# sk6812-24-12ring-in.net
KiCad netlist of a schematic drawn in EAGLE
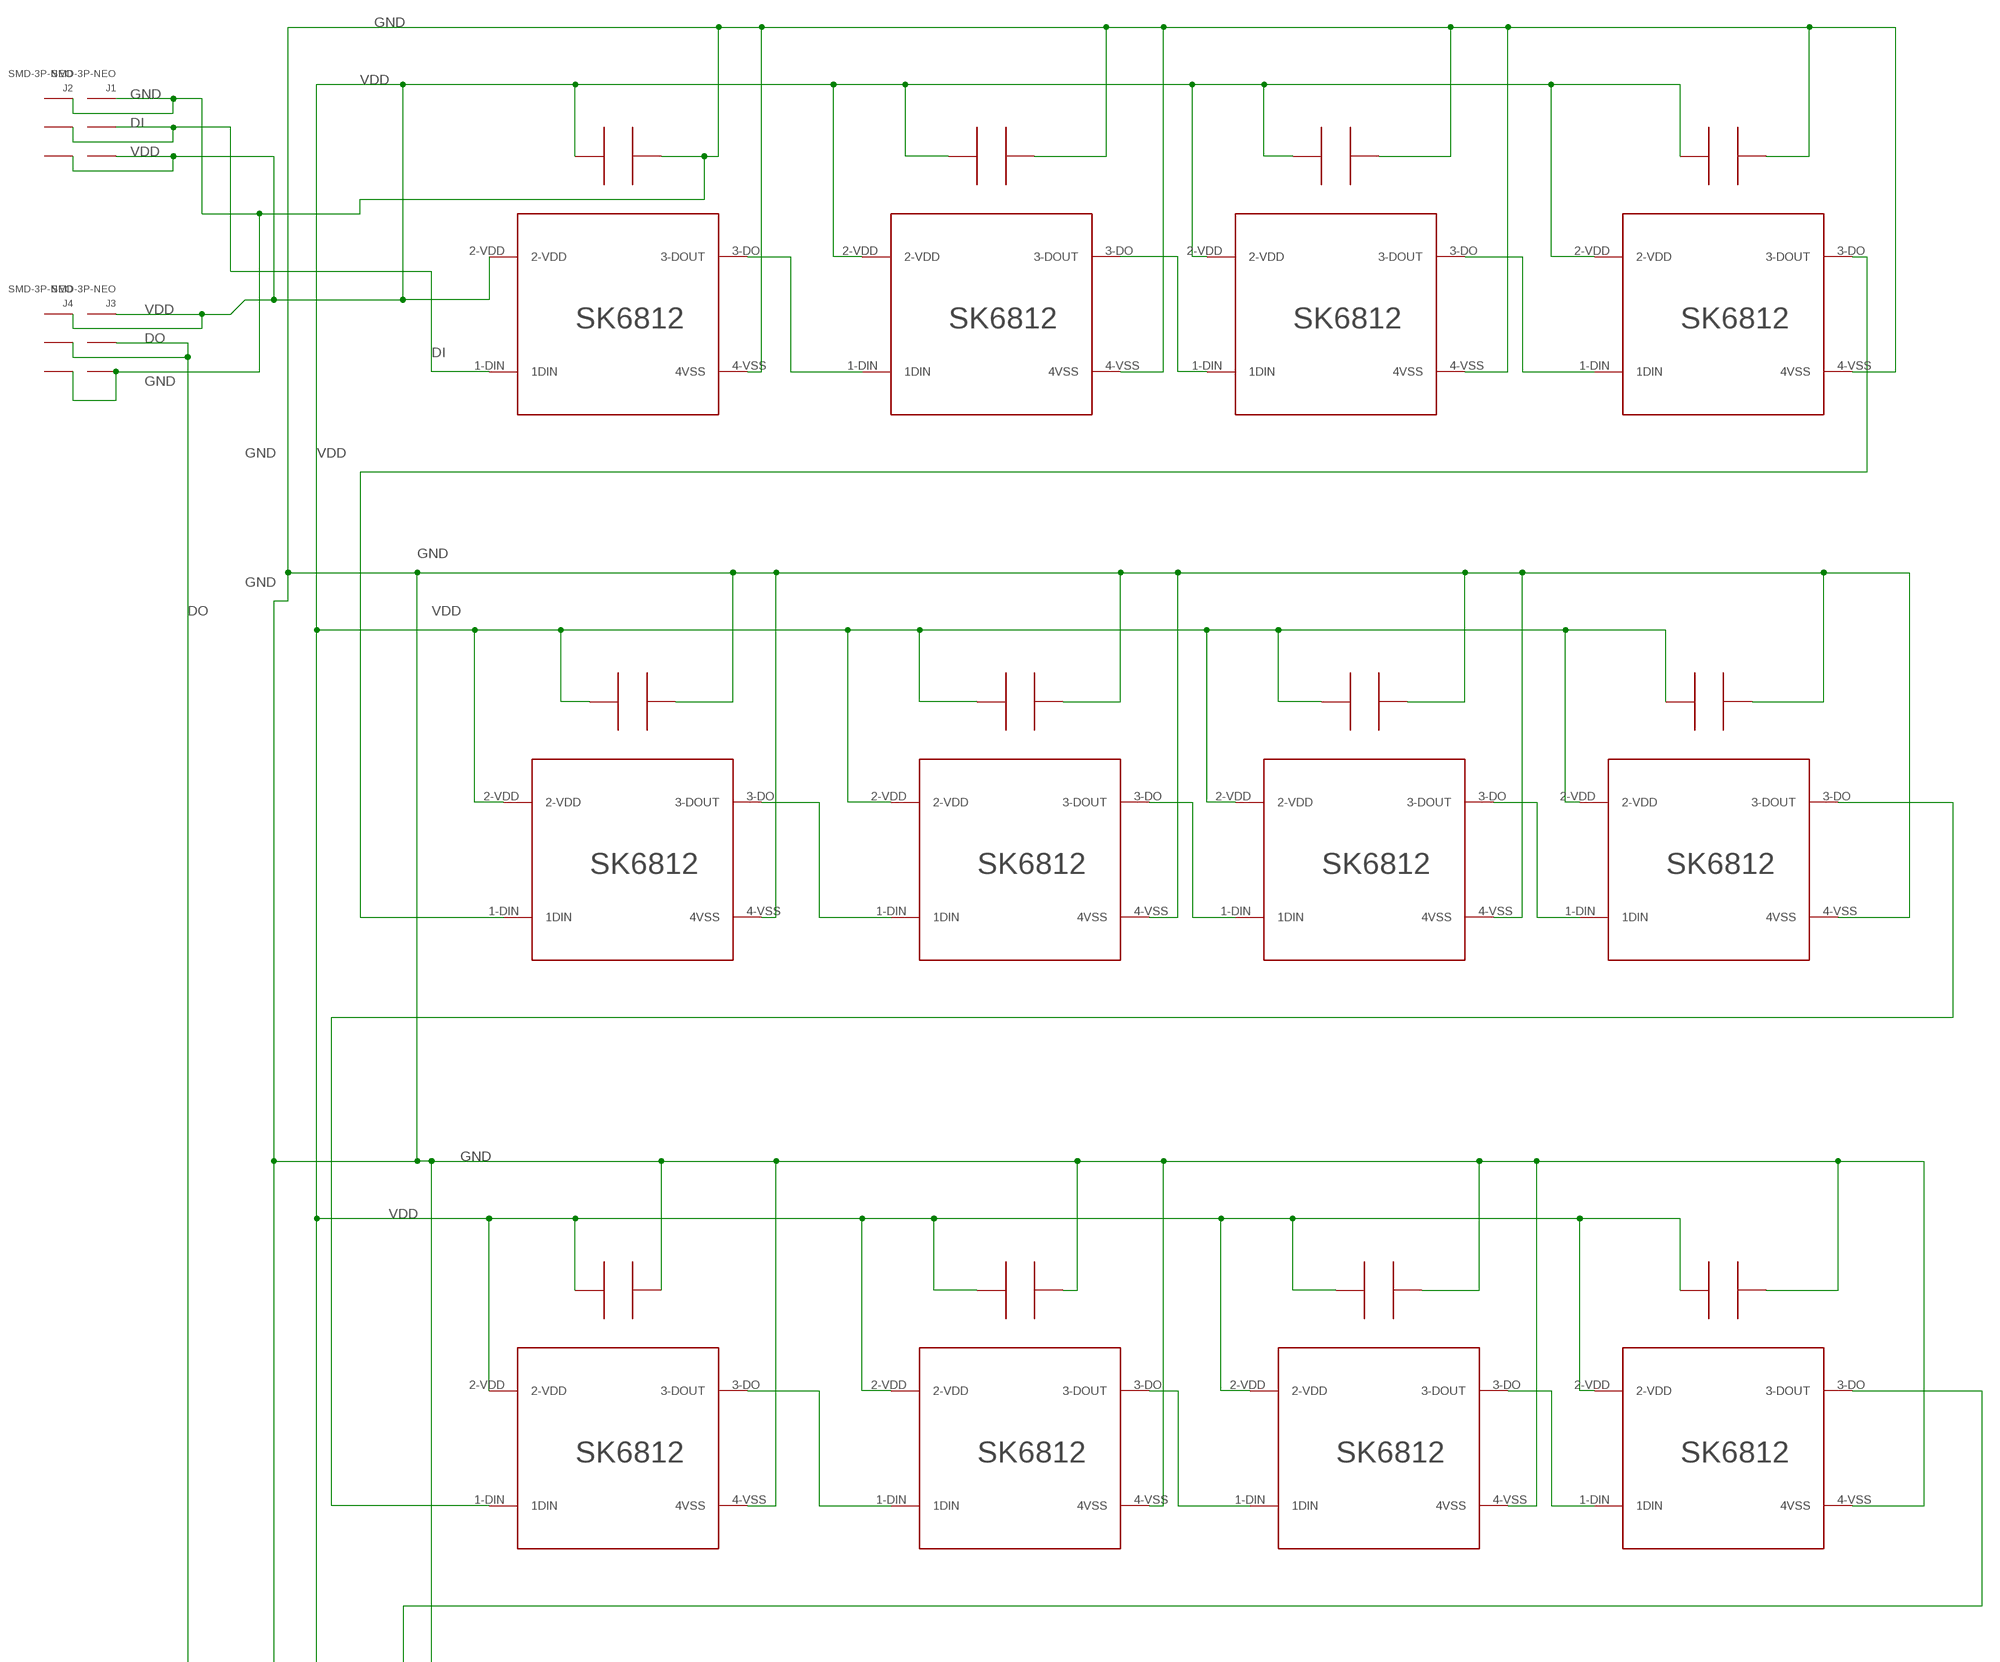
[diagram p0: schematic, sheet 1, part 1 of 2]
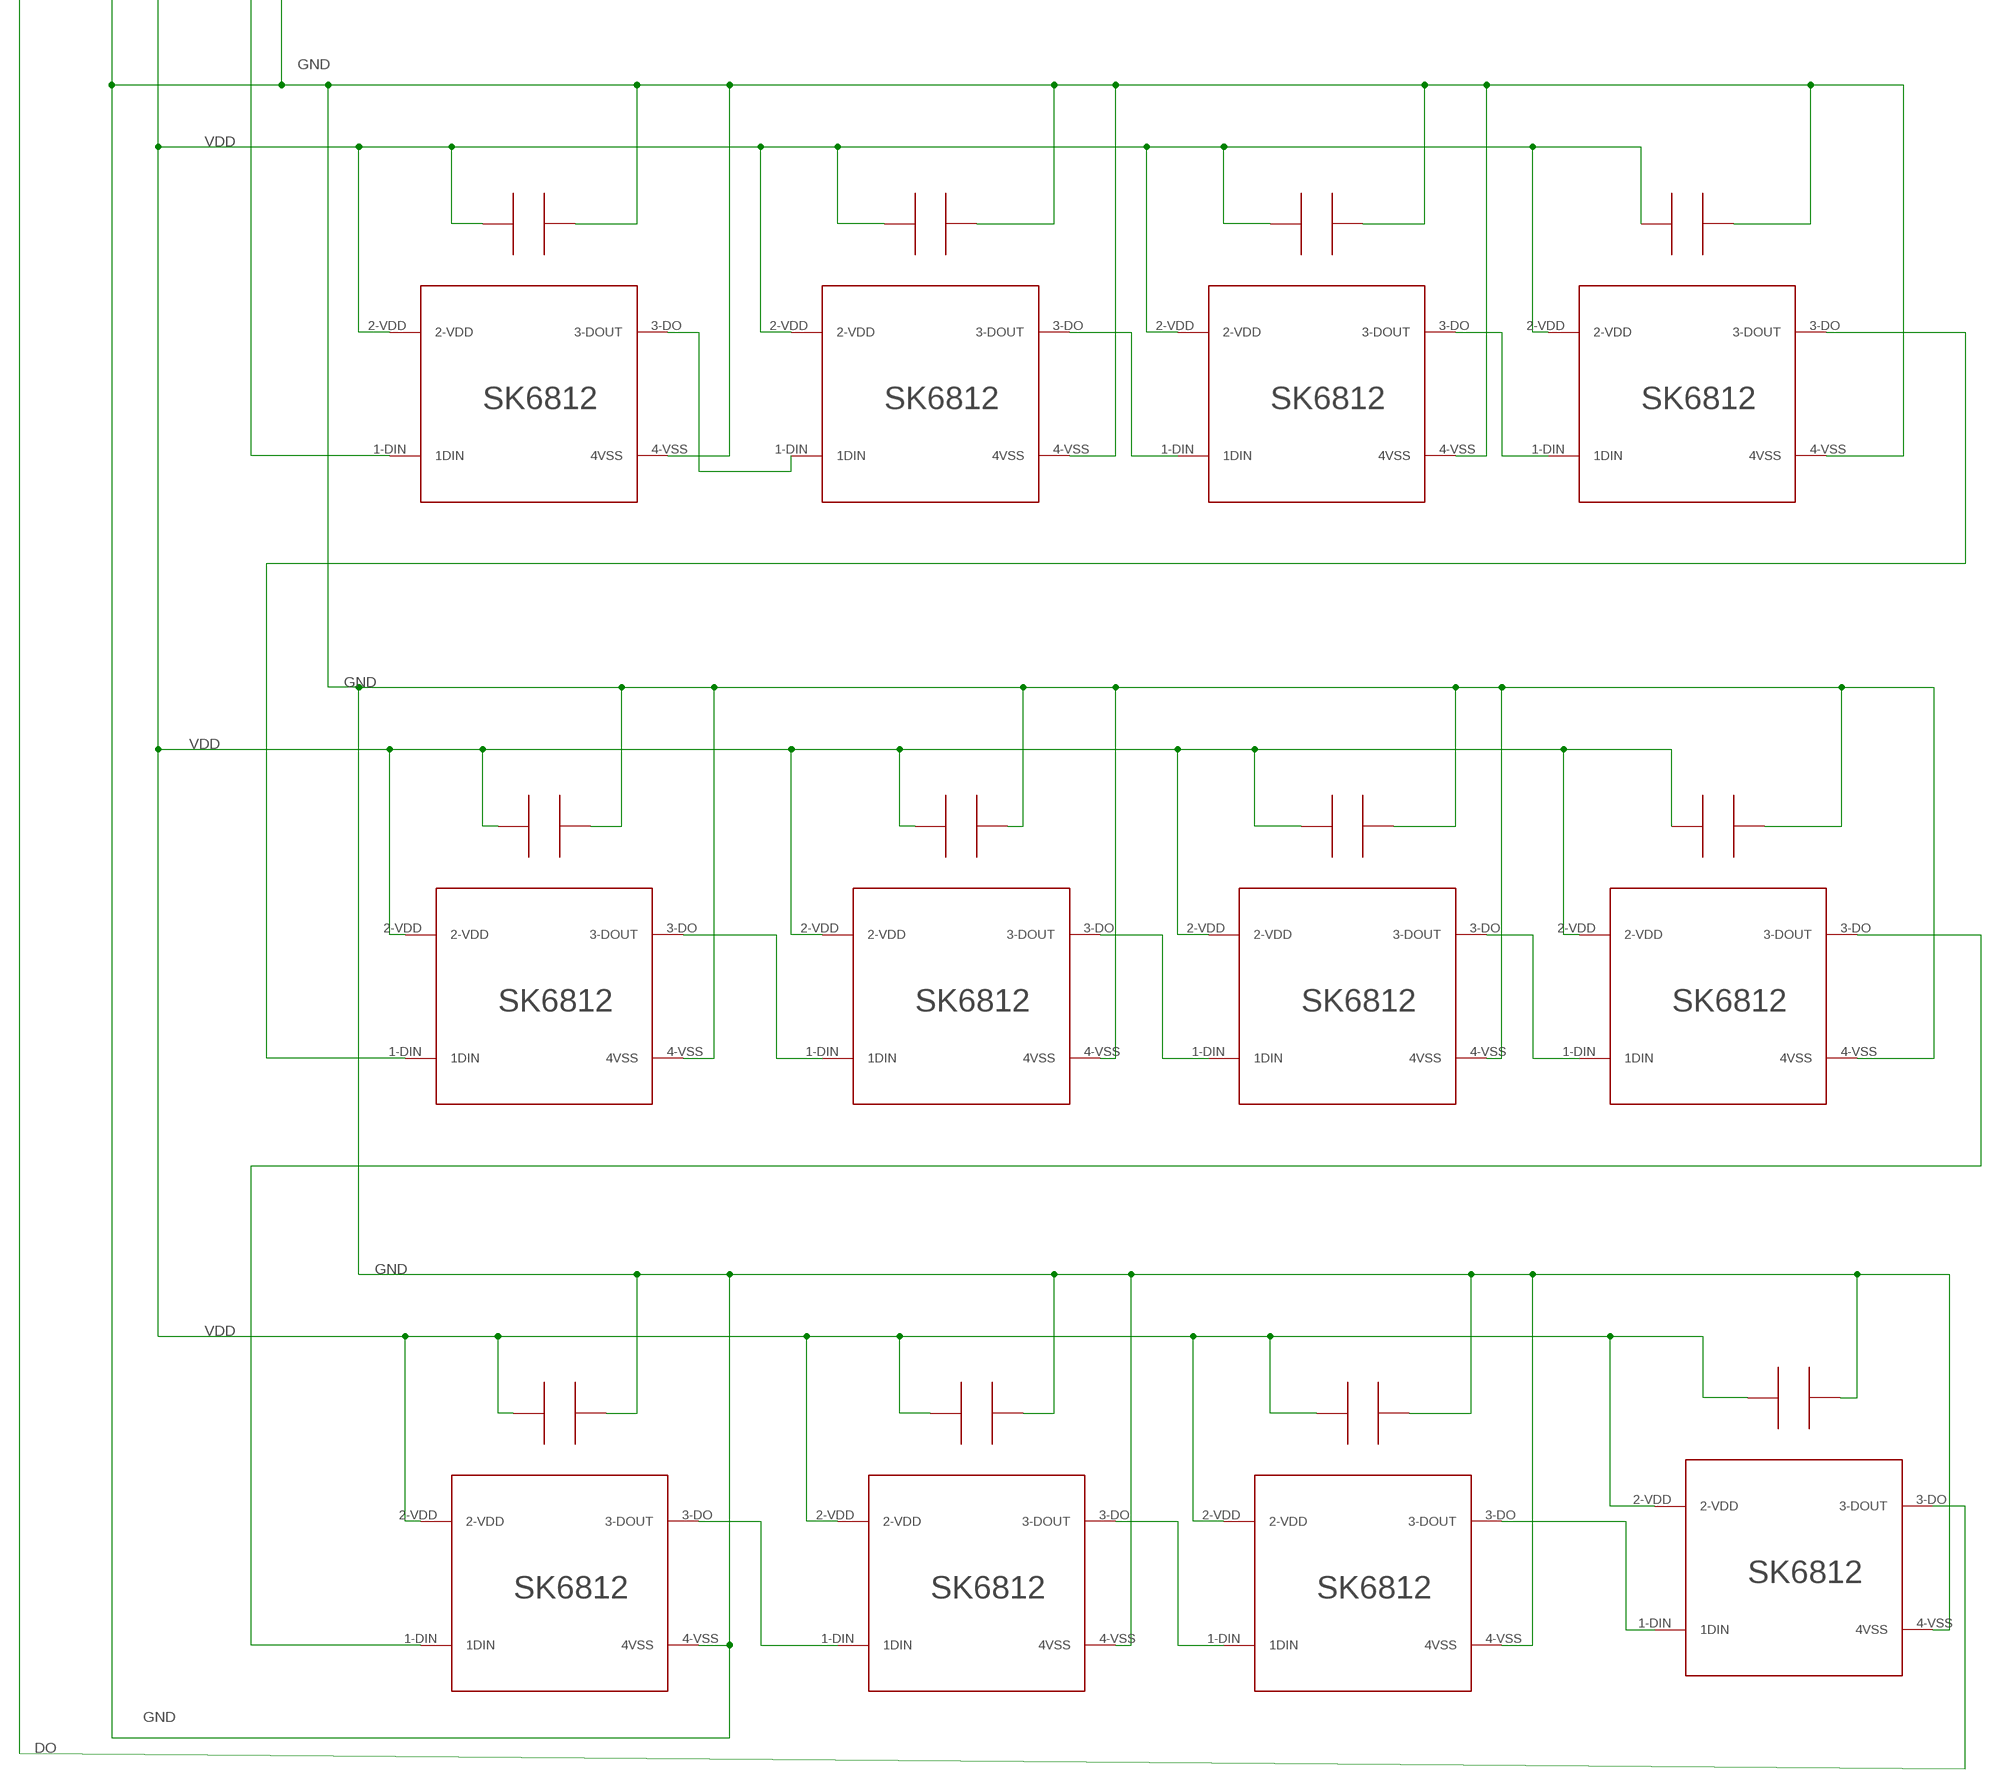
[diagram p1: schematic, sheet 1, part 2 of 2]

(export (version "E")
  (design (tool "Eeschema 10.0.6"))
  (components
    (comp (ref "D1")
      (value "SK6812-S-C")
      (footprint "eagle-import:SMD4020+0402C")
      (libsource (lib "eagle-import") (part "SK6812-S-C"))
    )
    (comp (ref "D2")
      (value "SK6812-S-C")
      (footprint "eagle-import:SMD4020+0402C")
      (libsource (lib "eagle-import") (part "SK6812-S-C"))
    )
    (comp (ref "D3")
      (value "SK6812-S-C")
      (footprint "eagle-import:SMD4020+0402C")
      (libsource (lib "eagle-import") (part "SK6812-S-C"))
    )
    (comp (ref "D4")
      (value "SK6812-S-C")
      (footprint "eagle-import:SMD4020+0402C")
      (libsource (lib "eagle-import") (part "SK6812-S-C"))
    )
    (comp (ref "D5")
      (value "SK6812-S-C")
      (footprint "eagle-import:SMD4020+0402C")
      (libsource (lib "eagle-import") (part "SK6812-S-C"))
    )
    (comp (ref "D6")
      (value "SK6812-S-C")
      (footprint "eagle-import:SMD4020+0402C")
      (libsource (lib "eagle-import") (part "SK6812-S-C"))
    )
    (comp (ref "D7")
      (value "SK6812-S-C")
      (footprint "eagle-import:SMD4020+0402C")
      (libsource (lib "eagle-import") (part "SK6812-S-C"))
    )
    (comp (ref "D8")
      (value "SK6812-S-C")
      (footprint "eagle-import:SMD4020+0402C")
      (libsource (lib "eagle-import") (part "SK6812-S-C"))
    )
    (comp (ref "D9")
      (value "SK6812-S-C")
      (footprint "eagle-import:SMD4020+0402C")
      (libsource (lib "eagle-import") (part "SK6812-S-C"))
    )
    (comp (ref "D10")
      (value "SK6812-S-C")
      (footprint "eagle-import:SMD4020+0402C")
      (libsource (lib "eagle-import") (part "SK6812-S-C"))
    )
    (comp (ref "D11")
      (value "SK6812-S-C")
      (footprint "eagle-import:SMD4020+0402C")
      (libsource (lib "eagle-import") (part "SK6812-S-C"))
    )
    (comp (ref "D12")
      (value "SK6812-S-C")
      (footprint "eagle-import:SMD4020+0402C")
      (libsource (lib "eagle-import") (part "SK6812-S-C"))
    )
    (comp (ref "D13")
      (value "SK6812-S-C")
      (footprint "eagle-import:SMD4020+0402C")
      (libsource (lib "eagle-import") (part "SK6812-S-C"))
    )
    (comp (ref "D14")
      (value "SK6812-S-C")
      (footprint "eagle-import:SMD4020+0402C")
      (libsource (lib "eagle-import") (part "SK6812-S-C"))
    )
    (comp (ref "D15")
      (value "SK6812-S-C")
      (footprint "eagle-import:SMD4020+0402C")
      (libsource (lib "eagle-import") (part "SK6812-S-C"))
    )
    (comp (ref "D16")
      (value "SK6812-S-C")
      (footprint "eagle-import:SMD4020+0402C")
      (libsource (lib "eagle-import") (part "SK6812-S-C"))
    )
    (comp (ref "D17")
      (value "SK6812-S-C")
      (footprint "eagle-import:SMD4020+0402C")
      (libsource (lib "eagle-import") (part "SK6812-S-C"))
    )
    (comp (ref "D18")
      (value "SK6812-S-C")
      (footprint "eagle-import:SMD4020+0402C")
      (libsource (lib "eagle-import") (part "SK6812-S-C"))
    )
    (comp (ref "D19")
      (value "SK6812-S-C")
      (footprint "eagle-import:SMD4020+0402C")
      (libsource (lib "eagle-import") (part "SK6812-S-C"))
    )
    (comp (ref "D20")
      (value "SK6812-S-C")
      (footprint "eagle-import:SMD4020+0402C")
      (libsource (lib "eagle-import") (part "SK6812-S-C"))
    )
    (comp (ref "D21")
      (value "SK6812-S-C")
      (footprint "eagle-import:SMD4020+0402C")
      (libsource (lib "eagle-import") (part "SK6812-S-C"))
    )
    (comp (ref "D22")
      (value "SK6812-S-C")
      (footprint "eagle-import:SMD4020+0402C")
      (libsource (lib "eagle-import") (part "SK6812-S-C"))
    )
    (comp (ref "D23")
      (value "SK6812-S-C")
      (footprint "eagle-import:SMD4020+0402C")
      (libsource (lib "eagle-import") (part "SK6812-S-C"))
    )
    (comp (ref "D24")
      (value "SK6812-S-C")
      (footprint "eagle-import:SMD4020+0402C")
      (libsource (lib "eagle-import") (part "SK6812-S-C"))
    )
    (comp (ref "J1")
      (value "SMD-3P-NEO")
      (footprint "eagle-import:SMD-3P-2.0")
      (libsource (lib "eagle-import") (part "SMD-3P-NEO"))
    )
    (comp (ref "J2")
      (value "SMD-3P-NEO")
      (footprint "eagle-import:SMD-3P-2.0")
      (libsource (lib "eagle-import") (part "SMD-3P-NEO"))
    )
    (comp (ref "J3")
      (value "SMD-3P-NEO")
      (footprint "eagle-import:SMD-3P-2.0")
      (libsource (lib "eagle-import") (part "SMD-3P-NEO"))
    )
    (comp (ref "J4")
      (value "SMD-3P-NEO")
      (footprint "eagle-import:SMD-3P-2.0")
      (libsource (lib "eagle-import") (part "SMD-3P-NEO"))
    )
  )
  (nets
    (net (code "1") (name "/DI") (class "Default")
      (node (ref "D1") (pin "1-DIN") (pinfunction "1DIN_1-DIN") (pintype "bidirectional"))
      (node (ref "J1") (pin "P$2") (pinfunction "2_P$2") (pintype "bidirectional"))
      (node (ref "J2") (pin "P$2") (pinfunction "2_P$2") (pintype "bidirectional"))
    )
    (net (code "2") (name "/DO") (class "Default")
      (node (ref "D24") (pin "3-DO") (pinfunction "3-DOUT_3-DO") (pintype "bidirectional"))
      (node (ref "J3") (pin "P$2") (pinfunction "2_P$2") (pintype "bidirectional"))
      (node (ref "J4") (pin "P$2") (pinfunction "2_P$2") (pintype "bidirectional"))
    )
    (net (code "3") (name "/GND") (class "Default")
      (node (ref "D1") (pin "4-VSS") (pinfunction "4VSS_4-VSS") (pintype "bidirectional"))
      (node (ref "D1") (pin "5-C-VSS") (pinfunction "C-VSS_5-C-VSS") (pintype "bidirectional"))
      (node (ref "D10") (pin "4-VSS") (pinfunction "4VSS_4-VSS") (pintype "bidirectional"))
      (node (ref "D10") (pin "5-C-VSS") (pinfunction "C-VSS_5-C-VSS") (pintype "bidirectional"))
      (node (ref "D11") (pin "4-VSS") (pinfunction "4VSS_4-VSS") (pintype "bidirectional"))
      (node (ref "D11") (pin "5-C-VSS") (pinfunction "C-VSS_5-C-VSS") (pintype "bidirectional"))
      (node (ref "D12") (pin "4-VSS") (pinfunction "4VSS_4-VSS") (pintype "bidirectional"))
      (node (ref "D12") (pin "5-C-VSS") (pinfunction "C-VSS_5-C-VSS") (pintype "bidirectional"))
      (node (ref "D13") (pin "4-VSS") (pinfunction "4VSS_4-VSS") (pintype "bidirectional"))
      (node (ref "D13") (pin "5-C-VSS") (pinfunction "C-VSS_5-C-VSS") (pintype "bidirectional"))
      (node (ref "D14") (pin "4-VSS") (pinfunction "4VSS_4-VSS") (pintype "bidirectional"))
      (node (ref "D14") (pin "5-C-VSS") (pinfunction "C-VSS_5-C-VSS") (pintype "bidirectional"))
      (node (ref "D15") (pin "4-VSS") (pinfunction "4VSS_4-VSS") (pintype "bidirectional"))
      (node (ref "D15") (pin "5-C-VSS") (pinfunction "C-VSS_5-C-VSS") (pintype "bidirectional"))
      (node (ref "D16") (pin "4-VSS") (pinfunction "4VSS_4-VSS") (pintype "bidirectional"))
      (node (ref "D16") (pin "5-C-VSS") (pinfunction "C-VSS_5-C-VSS") (pintype "bidirectional"))
      (node (ref "D17") (pin "4-VSS") (pinfunction "4VSS_4-VSS") (pintype "bidirectional"))
      (node (ref "D17") (pin "5-C-VSS") (pinfunction "C-VSS_5-C-VSS") (pintype "bidirectional"))
      (node (ref "D18") (pin "4-VSS") (pinfunction "4VSS_4-VSS") (pintype "bidirectional"))
      (node (ref "D18") (pin "5-C-VSS") (pinfunction "C-VSS_5-C-VSS") (pintype "bidirectional"))
      (node (ref "D19") (pin "4-VSS") (pinfunction "4VSS_4-VSS") (pintype "bidirectional"))
      (node (ref "D19") (pin "5-C-VSS") (pinfunction "C-VSS_5-C-VSS") (pintype "bidirectional"))
      (node (ref "D2") (pin "4-VSS") (pinfunction "4VSS_4-VSS") (pintype "bidirectional"))
      (node (ref "D2") (pin "5-C-VSS") (pinfunction "C-VSS_5-C-VSS") (pintype "bidirectional"))
      (node (ref "D20") (pin "4-VSS") (pinfunction "4VSS_4-VSS") (pintype "bidirectional"))
      (node (ref "D20") (pin "5-C-VSS") (pinfunction "C-VSS_5-C-VSS") (pintype "bidirectional"))
      (node (ref "D21") (pin "4-VSS") (pinfunction "4VSS_4-VSS") (pintype "bidirectional"))
      (node (ref "D21") (pin "5-C-VSS") (pinfunction "C-VSS_5-C-VSS") (pintype "bidirectional"))
      (node (ref "D22") (pin "4-VSS") (pinfunction "4VSS_4-VSS") (pintype "bidirectional"))
      (node (ref "D22") (pin "5-C-VSS") (pinfunction "C-VSS_5-C-VSS") (pintype "bidirectional"))
      (node (ref "D23") (pin "4-VSS") (pinfunction "4VSS_4-VSS") (pintype "bidirectional"))
      (node (ref "D23") (pin "5-C-VSS") (pinfunction "C-VSS_5-C-VSS") (pintype "bidirectional"))
      (node (ref "D24") (pin "4-VSS") (pinfunction "4VSS_4-VSS") (pintype "bidirectional"))
      (node (ref "D24") (pin "5-C-VSS") (pinfunction "C-VSS_5-C-VSS") (pintype "bidirectional"))
      (node (ref "D3") (pin "4-VSS") (pinfunction "4VSS_4-VSS") (pintype "bidirectional"))
      (node (ref "D3") (pin "5-C-VSS") (pinfunction "C-VSS_5-C-VSS") (pintype "bidirectional"))
      (node (ref "D4") (pin "4-VSS") (pinfunction "4VSS_4-VSS") (pintype "bidirectional"))
      (node (ref "D4") (pin "5-C-VSS") (pinfunction "C-VSS_5-C-VSS") (pintype "bidirectional"))
      (node (ref "D5") (pin "4-VSS") (pinfunction "4VSS_4-VSS") (pintype "bidirectional"))
      (node (ref "D5") (pin "5-C-VSS") (pinfunction "C-VSS_5-C-VSS") (pintype "bidirectional"))
      (node (ref "D6") (pin "4-VSS") (pinfunction "4VSS_4-VSS") (pintype "bidirectional"))
      (node (ref "D6") (pin "5-C-VSS") (pinfunction "C-VSS_5-C-VSS") (pintype "bidirectional"))
      (node (ref "D7") (pin "4-VSS") (pinfunction "4VSS_4-VSS") (pintype "bidirectional"))
      (node (ref "D7") (pin "5-C-VSS") (pinfunction "C-VSS_5-C-VSS") (pintype "bidirectional"))
      (node (ref "D8") (pin "4-VSS") (pinfunction "4VSS_4-VSS") (pintype "bidirectional"))
      (node (ref "D8") (pin "5-C-VSS") (pinfunction "C-VSS_5-C-VSS") (pintype "bidirectional"))
      (node (ref "D9") (pin "4-VSS") (pinfunction "4VSS_4-VSS") (pintype "bidirectional"))
      (node (ref "D9") (pin "5-C-VSS") (pinfunction "C-VSS_5-C-VSS") (pintype "bidirectional"))
      (node (ref "J1") (pin "P$3") (pinfunction "3_P$3") (pintype "bidirectional"))
      (node (ref "J2") (pin "P$3") (pinfunction "3_P$3") (pintype "bidirectional"))
      (node (ref "J3") (pin "P$1") (pinfunction "1_P$1") (pintype "bidirectional"))
      (node (ref "J4") (pin "P$1") (pinfunction "1_P$1") (pintype "bidirectional"))
    )
    (net (code "4") (name "/VDD") (class "Default")
      (node (ref "D1") (pin "2-VDD") (pinfunction "2-VDD_2-VDD") (pintype "bidirectional"))
      (node (ref "D1") (pin "6-C-VDD") (pinfunction "C-VDD_6-C-VDD") (pintype "bidirectional"))
      (node (ref "D10") (pin "2-VDD") (pinfunction "2-VDD_2-VDD") (pintype "bidirectional"))
      (node (ref "D10") (pin "6-C-VDD") (pinfunction "C-VDD_6-C-VDD") (pintype "bidirectional"))
      (node (ref "D11") (pin "2-VDD") (pinfunction "2-VDD_2-VDD") (pintype "bidirectional"))
      (node (ref "D11") (pin "6-C-VDD") (pinfunction "C-VDD_6-C-VDD") (pintype "bidirectional"))
      (node (ref "D12") (pin "2-VDD") (pinfunction "2-VDD_2-VDD") (pintype "bidirectional"))
      (node (ref "D12") (pin "6-C-VDD") (pinfunction "C-VDD_6-C-VDD") (pintype "bidirectional"))
      (node (ref "D13") (pin "2-VDD") (pinfunction "2-VDD_2-VDD") (pintype "bidirectional"))
      (node (ref "D13") (pin "6-C-VDD") (pinfunction "C-VDD_6-C-VDD") (pintype "bidirectional"))
      (node (ref "D14") (pin "2-VDD") (pinfunction "2-VDD_2-VDD") (pintype "bidirectional"))
      (node (ref "D14") (pin "6-C-VDD") (pinfunction "C-VDD_6-C-VDD") (pintype "bidirectional"))
      (node (ref "D15") (pin "2-VDD") (pinfunction "2-VDD_2-VDD") (pintype "bidirectional"))
      (node (ref "D15") (pin "6-C-VDD") (pinfunction "C-VDD_6-C-VDD") (pintype "bidirectional"))
      (node (ref "D16") (pin "2-VDD") (pinfunction "2-VDD_2-VDD") (pintype "bidirectional"))
      (node (ref "D16") (pin "6-C-VDD") (pinfunction "C-VDD_6-C-VDD") (pintype "bidirectional"))
      (node (ref "D17") (pin "2-VDD") (pinfunction "2-VDD_2-VDD") (pintype "bidirectional"))
      (node (ref "D17") (pin "6-C-VDD") (pinfunction "C-VDD_6-C-VDD") (pintype "bidirectional"))
      (node (ref "D18") (pin "2-VDD") (pinfunction "2-VDD_2-VDD") (pintype "bidirectional"))
      (node (ref "D18") (pin "6-C-VDD") (pinfunction "C-VDD_6-C-VDD") (pintype "bidirectional"))
      (node (ref "D19") (pin "2-VDD") (pinfunction "2-VDD_2-VDD") (pintype "bidirectional"))
      (node (ref "D19") (pin "6-C-VDD") (pinfunction "C-VDD_6-C-VDD") (pintype "bidirectional"))
      (node (ref "D2") (pin "2-VDD") (pinfunction "2-VDD_2-VDD") (pintype "bidirectional"))
      (node (ref "D2") (pin "6-C-VDD") (pinfunction "C-VDD_6-C-VDD") (pintype "bidirectional"))
      (node (ref "D20") (pin "2-VDD") (pinfunction "2-VDD_2-VDD") (pintype "bidirectional"))
      (node (ref "D20") (pin "6-C-VDD") (pinfunction "C-VDD_6-C-VDD") (pintype "bidirectional"))
      (node (ref "D21") (pin "2-VDD") (pinfunction "2-VDD_2-VDD") (pintype "bidirectional"))
      (node (ref "D21") (pin "6-C-VDD") (pinfunction "C-VDD_6-C-VDD") (pintype "bidirectional"))
      (node (ref "D22") (pin "2-VDD") (pinfunction "2-VDD_2-VDD") (pintype "bidirectional"))
      (node (ref "D22") (pin "6-C-VDD") (pinfunction "C-VDD_6-C-VDD") (pintype "bidirectional"))
      (node (ref "D23") (pin "2-VDD") (pinfunction "2-VDD_2-VDD") (pintype "bidirectional"))
      (node (ref "D23") (pin "6-C-VDD") (pinfunction "C-VDD_6-C-VDD") (pintype "bidirectional"))
      (node (ref "D24") (pin "2-VDD") (pinfunction "2-VDD_2-VDD") (pintype "bidirectional"))
      (node (ref "D24") (pin "6-C-VDD") (pinfunction "C-VDD_6-C-VDD") (pintype "bidirectional"))
      (node (ref "D3") (pin "2-VDD") (pinfunction "2-VDD_2-VDD") (pintype "bidirectional"))
      (node (ref "D3") (pin "6-C-VDD") (pinfunction "C-VDD_6-C-VDD") (pintype "bidirectional"))
      (node (ref "D4") (pin "2-VDD") (pinfunction "2-VDD_2-VDD") (pintype "bidirectional"))
      (node (ref "D4") (pin "6-C-VDD") (pinfunction "C-VDD_6-C-VDD") (pintype "bidirectional"))
      (node (ref "D5") (pin "2-VDD") (pinfunction "2-VDD_2-VDD") (pintype "bidirectional"))
      (node (ref "D5") (pin "6-C-VDD") (pinfunction "C-VDD_6-C-VDD") (pintype "bidirectional"))
      (node (ref "D6") (pin "2-VDD") (pinfunction "2-VDD_2-VDD") (pintype "bidirectional"))
      (node (ref "D6") (pin "6-C-VDD") (pinfunction "C-VDD_6-C-VDD") (pintype "bidirectional"))
      (node (ref "D7") (pin "2-VDD") (pinfunction "2-VDD_2-VDD") (pintype "bidirectional"))
      (node (ref "D7") (pin "6-C-VDD") (pinfunction "C-VDD_6-C-VDD") (pintype "bidirectional"))
      (node (ref "D8") (pin "2-VDD") (pinfunction "2-VDD_2-VDD") (pintype "bidirectional"))
      (node (ref "D8") (pin "6-C-VDD") (pinfunction "C-VDD_6-C-VDD") (pintype "bidirectional"))
      (node (ref "D9") (pin "2-VDD") (pinfunction "2-VDD_2-VDD") (pintype "bidirectional"))
      (node (ref "D9") (pin "6-C-VDD") (pinfunction "C-VDD_6-C-VDD") (pintype "bidirectional"))
      (node (ref "J1") (pin "P$1") (pinfunction "1_P$1") (pintype "bidirectional"))
      (node (ref "J2") (pin "P$1") (pinfunction "1_P$1") (pintype "bidirectional"))
      (node (ref "J3") (pin "P$3") (pinfunction "3_P$3") (pintype "bidirectional"))
      (node (ref "J4") (pin "P$3") (pinfunction "3_P$3") (pintype "bidirectional"))
    )
    (net (code "5") (name "Net-(D1-3-DOUT)") (class "Default")
      (node (ref "D1") (pin "3-DO") (pinfunction "3-DOUT_3-DO") (pintype "bidirectional"))
      (node (ref "D2") (pin "1-DIN") (pinfunction "1DIN_1-DIN") (pintype "bidirectional"))
    )
    (net (code "6") (name "Net-(D2-3-DOUT)") (class "Default")
      (node (ref "D2") (pin "3-DO") (pinfunction "3-DOUT_3-DO") (pintype "bidirectional"))
      (node (ref "D3") (pin "1-DIN") (pinfunction "1DIN_1-DIN") (pintype "bidirectional"))
    )
    (net (code "7") (name "Net-(D3-3-DOUT)") (class "Default")
      (node (ref "D3") (pin "3-DO") (pinfunction "3-DOUT_3-DO") (pintype "bidirectional"))
      (node (ref "D4") (pin "1-DIN") (pinfunction "1DIN_1-DIN") (pintype "bidirectional"))
    )
    (net (code "8") (name "Net-(D4-3-DOUT)") (class "Default")
      (node (ref "D4") (pin "3-DO") (pinfunction "3-DOUT_3-DO") (pintype "bidirectional"))
      (node (ref "D5") (pin "1-DIN") (pinfunction "1DIN_1-DIN") (pintype "bidirectional"))
    )
    (net (code "9") (name "Net-(D5-3-DOUT)") (class "Default")
      (node (ref "D5") (pin "3-DO") (pinfunction "3-DOUT_3-DO") (pintype "bidirectional"))
      (node (ref "D6") (pin "1-DIN") (pinfunction "1DIN_1-DIN") (pintype "bidirectional"))
    )
    (net (code "10") (name "Net-(D6-3-DOUT)") (class "Default")
      (node (ref "D6") (pin "3-DO") (pinfunction "3-DOUT_3-DO") (pintype "bidirectional"))
      (node (ref "D7") (pin "1-DIN") (pinfunction "1DIN_1-DIN") (pintype "bidirectional"))
    )
    (net (code "11") (name "Net-(D7-3-DOUT)") (class "Default")
      (node (ref "D7") (pin "3-DO") (pinfunction "3-DOUT_3-DO") (pintype "bidirectional"))
      (node (ref "D8") (pin "1-DIN") (pinfunction "1DIN_1-DIN") (pintype "bidirectional"))
    )
    (net (code "12") (name "Net-(D8-3-DOUT)") (class "Default")
      (node (ref "D8") (pin "3-DO") (pinfunction "3-DOUT_3-DO") (pintype "bidirectional"))
      (node (ref "D9") (pin "1-DIN") (pinfunction "1DIN_1-DIN") (pintype "bidirectional"))
    )
    (net (code "13") (name "Net-(D10-1DIN)") (class "Default")
      (node (ref "D10") (pin "1-DIN") (pinfunction "1DIN_1-DIN") (pintype "bidirectional"))
      (node (ref "D9") (pin "3-DO") (pinfunction "3-DOUT_3-DO") (pintype "bidirectional"))
    )
    (net (code "14") (name "Net-(D10-3-DOUT)") (class "Default")
      (node (ref "D10") (pin "3-DO") (pinfunction "3-DOUT_3-DO") (pintype "bidirectional"))
      (node (ref "D11") (pin "1-DIN") (pinfunction "1DIN_1-DIN") (pintype "bidirectional"))
    )
    (net (code "15") (name "Net-(D11-3-DOUT)") (class "Default")
      (node (ref "D11") (pin "3-DO") (pinfunction "3-DOUT_3-DO") (pintype "bidirectional"))
      (node (ref "D12") (pin "1-DIN") (pinfunction "1DIN_1-DIN") (pintype "bidirectional"))
    )
    (net (code "16") (name "Net-(D12-3-DOUT)") (class "Default")
      (node (ref "D12") (pin "3-DO") (pinfunction "3-DOUT_3-DO") (pintype "bidirectional"))
      (node (ref "D13") (pin "1-DIN") (pinfunction "1DIN_1-DIN") (pintype "bidirectional"))
    )
    (net (code "17") (name "Net-(D13-3-DOUT)") (class "Default")
      (node (ref "D13") (pin "3-DO") (pinfunction "3-DOUT_3-DO") (pintype "bidirectional"))
      (node (ref "D14") (pin "1-DIN") (pinfunction "1DIN_1-DIN") (pintype "bidirectional"))
    )
    (net (code "18") (name "Net-(D14-3-DOUT)") (class "Default")
      (node (ref "D14") (pin "3-DO") (pinfunction "3-DOUT_3-DO") (pintype "bidirectional"))
      (node (ref "D15") (pin "1-DIN") (pinfunction "1DIN_1-DIN") (pintype "bidirectional"))
    )
    (net (code "19") (name "Net-(D15-3-DOUT)") (class "Default")
      (node (ref "D15") (pin "3-DO") (pinfunction "3-DOUT_3-DO") (pintype "bidirectional"))
      (node (ref "D16") (pin "1-DIN") (pinfunction "1DIN_1-DIN") (pintype "bidirectional"))
    )
    (net (code "20") (name "Net-(D16-3-DOUT)") (class "Default")
      (node (ref "D16") (pin "3-DO") (pinfunction "3-DOUT_3-DO") (pintype "bidirectional"))
      (node (ref "D17") (pin "1-DIN") (pinfunction "1DIN_1-DIN") (pintype "bidirectional"))
    )
    (net (code "21") (name "Net-(D17-3-DOUT)") (class "Default")
      (node (ref "D17") (pin "3-DO") (pinfunction "3-DOUT_3-DO") (pintype "bidirectional"))
      (node (ref "D18") (pin "1-DIN") (pinfunction "1DIN_1-DIN") (pintype "bidirectional"))
    )
    (net (code "22") (name "Net-(D18-3-DOUT)") (class "Default")
      (node (ref "D18") (pin "3-DO") (pinfunction "3-DOUT_3-DO") (pintype "bidirectional"))
      (node (ref "D19") (pin "1-DIN") (pinfunction "1DIN_1-DIN") (pintype "bidirectional"))
    )
    (net (code "23") (name "Net-(D19-3-DOUT)") (class "Default")
      (node (ref "D19") (pin "3-DO") (pinfunction "3-DOUT_3-DO") (pintype "bidirectional"))
      (node (ref "D20") (pin "1-DIN") (pinfunction "1DIN_1-DIN") (pintype "bidirectional"))
    )
    (net (code "24") (name "Net-(D20-3-DOUT)") (class "Default")
      (node (ref "D20") (pin "3-DO") (pinfunction "3-DOUT_3-DO") (pintype "bidirectional"))
      (node (ref "D21") (pin "1-DIN") (pinfunction "1DIN_1-DIN") (pintype "bidirectional"))
    )
    (net (code "25") (name "Net-(D21-3-DOUT)") (class "Default")
      (node (ref "D21") (pin "3-DO") (pinfunction "3-DOUT_3-DO") (pintype "bidirectional"))
      (node (ref "D22") (pin "1-DIN") (pinfunction "1DIN_1-DIN") (pintype "bidirectional"))
    )
    (net (code "26") (name "Net-(D22-3-DOUT)") (class "Default")
      (node (ref "D22") (pin "3-DO") (pinfunction "3-DOUT_3-DO") (pintype "bidirectional"))
      (node (ref "D23") (pin "1-DIN") (pinfunction "1DIN_1-DIN") (pintype "bidirectional"))
    )
    (net (code "27") (name "Net-(D23-3-DOUT)") (class "Default")
      (node (ref "D23") (pin "3-DO") (pinfunction "3-DOUT_3-DO") (pintype "bidirectional"))
      (node (ref "D24") (pin "1-DIN") (pinfunction "1DIN_1-DIN") (pintype "bidirectional"))
    )
  )
)
